# Sh_core.net
KiCad netlist of a schematic drawn in Altium Designer
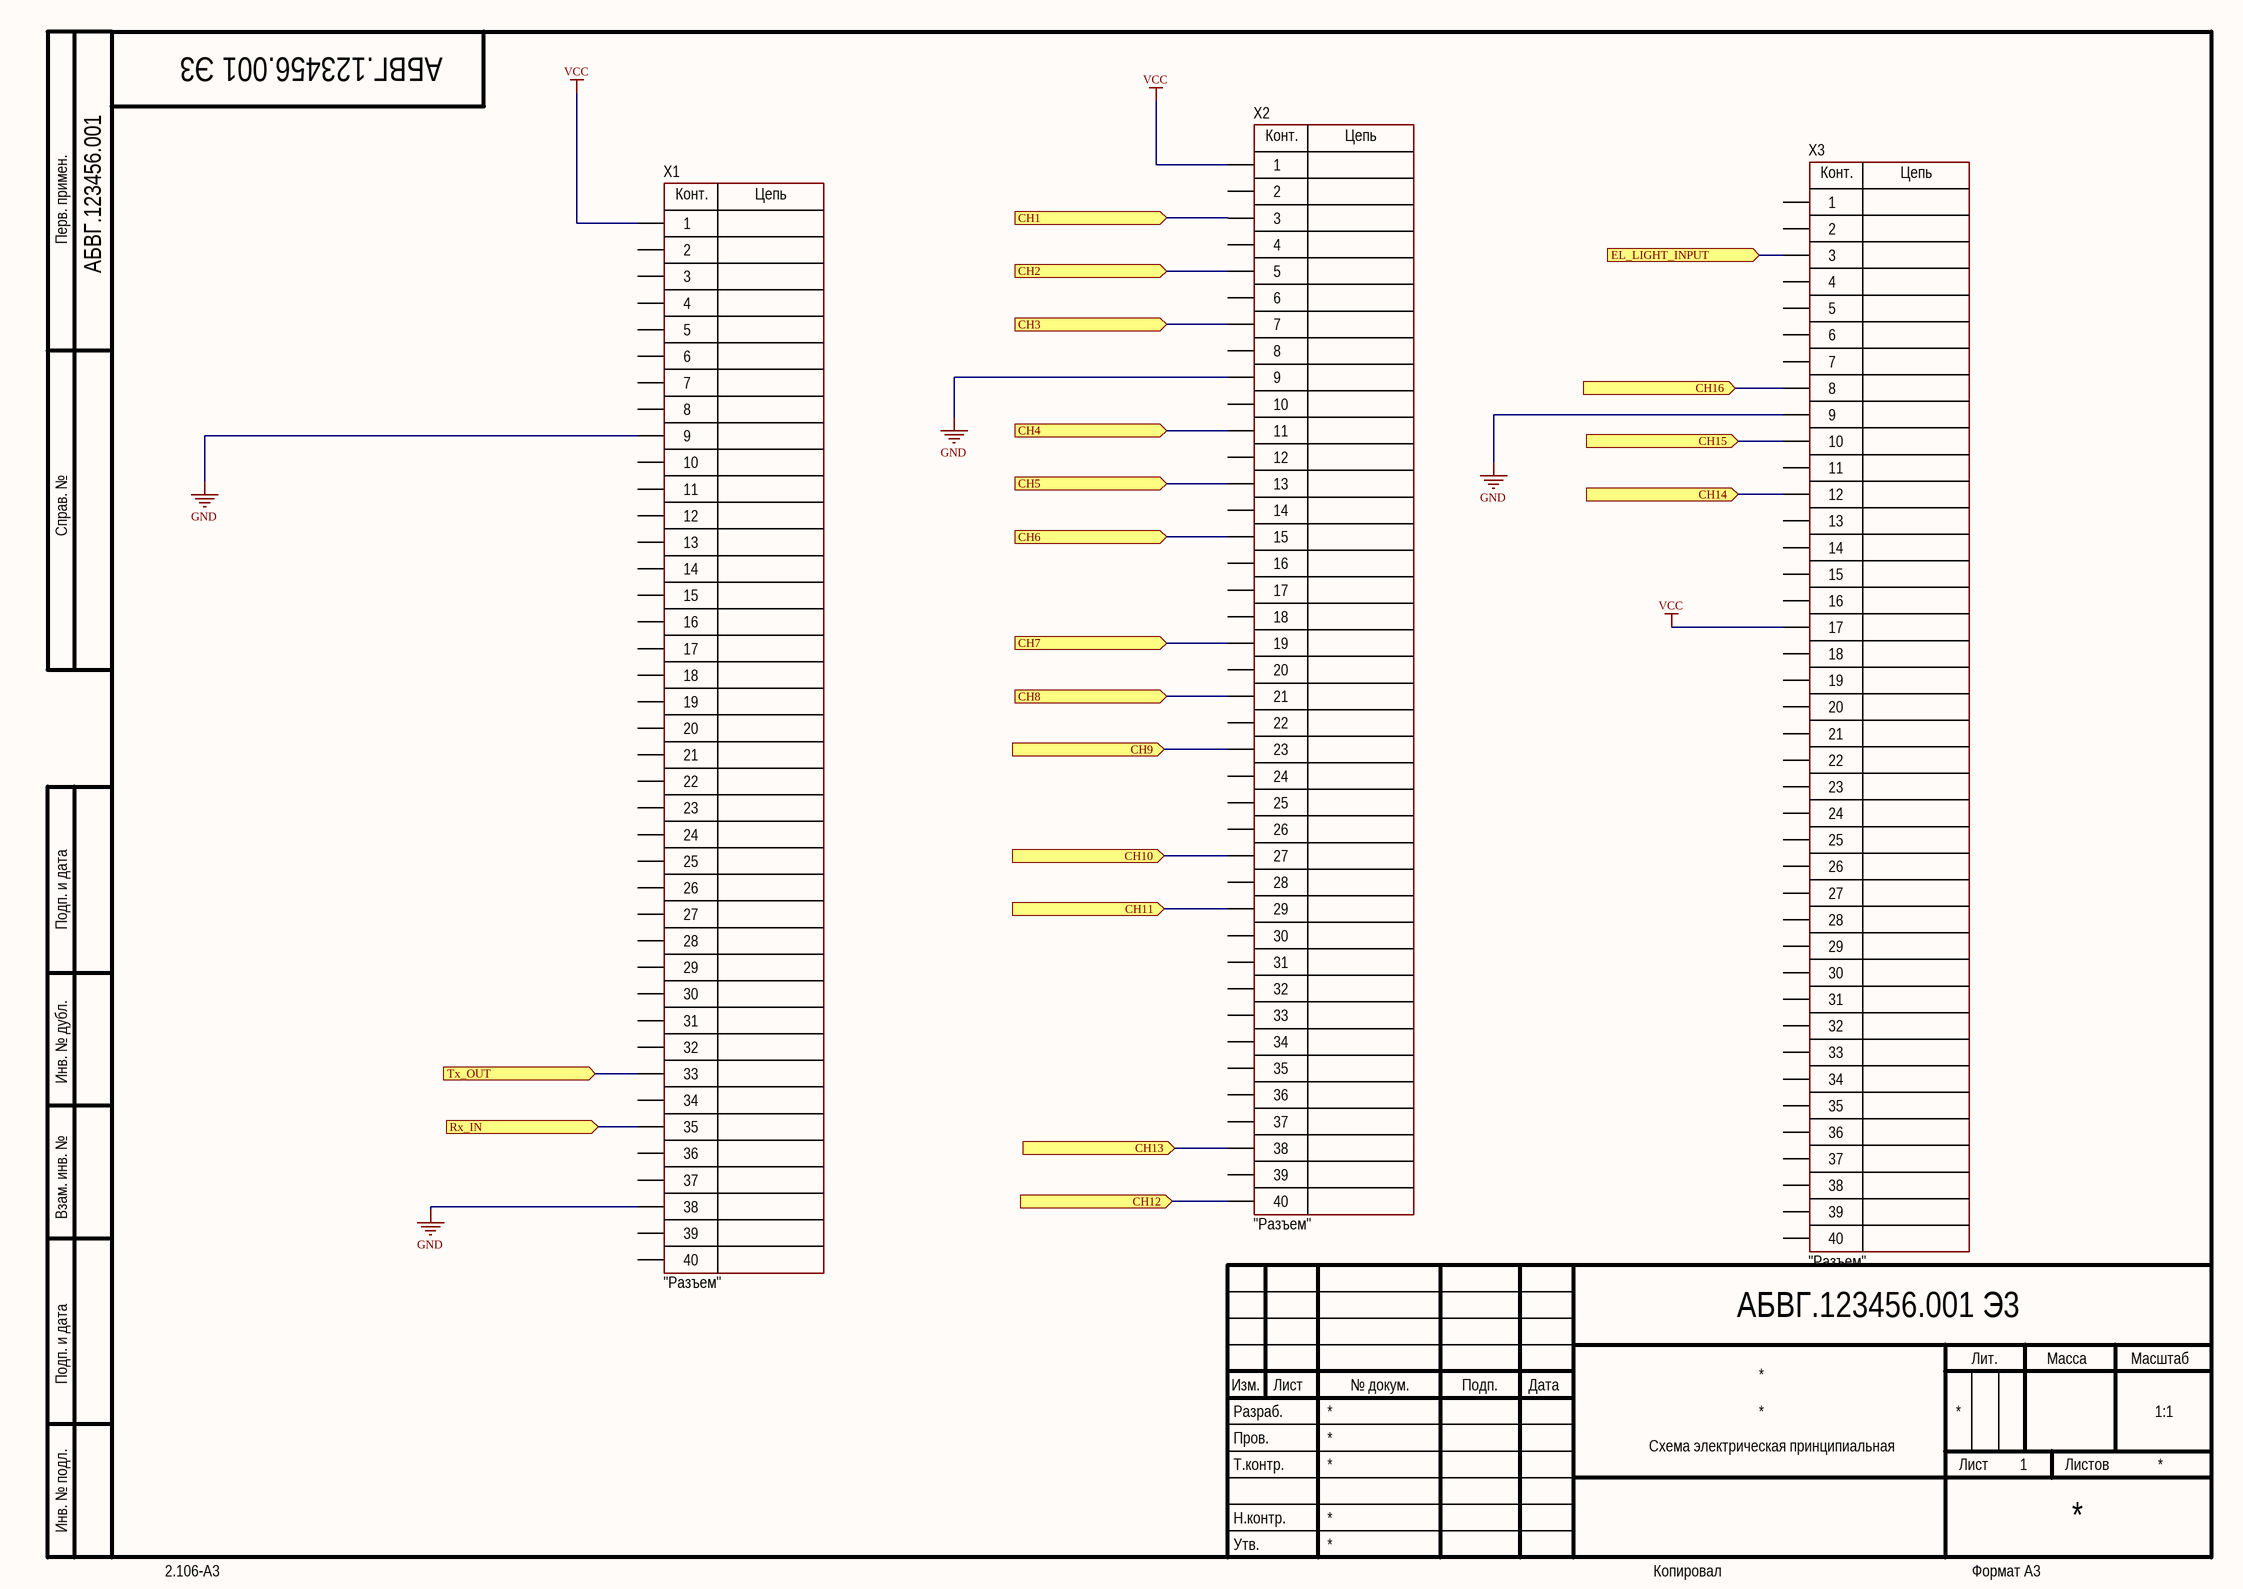
[diagram p0: Sh_core.SchDoc]

(export (version "E")
  (design (tool "Eeschema 10.0.6"))
  (components
    (comp (ref "X1")
      (value "~")
      (footprint "CON: PBD-40 (2.54)")
      (fields
        (field (name "MANUFACTURER") "Connfly")
        (field (name "VALUEMANUFACTURERPARTNUMBER") "Connector, 20pin, 2.54mm, 500VAC, 3A")
        (field (name "PARTNUMBER") "PLS-20")
        (field (name "COMMENTTEXT") "\"Разъем\"")
      )
      (libsource (lib "connector") (part "PBD-40"))
    )
    (comp (ref "X2")
      (value "~")
      (footprint "CON: PBD-40 (2.54)")
      (fields
        (field (name "MANUFACTURER") "Connfly")
        (field (name "VALUEMANUFACTURERPARTNUMBER") "Connector, 20pin, 2.54mm, 500VAC, 3A")
        (field (name "PARTNUMBER") "PLS-20")
        (field (name "COMMENTTEXT") "\"Разъем\"")
      )
      (libsource (lib "connector") (part "PBD-40"))
    )
    (comp (ref "X3")
      (value "~")
      (footprint "CON: PBD-40 (2.54)")
      (fields
        (field (name "MANUFACTURER") "Connfly")
        (field (name "VALUEMANUFACTURERPARTNUMBER") "Connector, 20pin, 2.54mm, 500VAC, 3A")
        (field (name "PARTNUMBER") "PLS-20")
        (field (name "COMMENTTEXT") "\"Разъем\"")
      )
      (libsource (lib "connector") (part "PBD-40"))
    )
  )
  (nets
    (net (code "1") (name "/CH1") (class "Default")
      (node (ref "X2") (pin "3") (pinfunction "3_3") (pintype "passive"))
    )
    (net (code "2") (name "/CH2") (class "Default")
      (node (ref "X2") (pin "5") (pinfunction "5_5") (pintype "passive"))
    )
    (net (code "3") (name "/CH3") (class "Default")
      (node (ref "X2") (pin "7") (pinfunction "7_7") (pintype "passive"))
    )
    (net (code "4") (name "/CH4") (class "Default")
      (node (ref "X2") (pin "11") (pinfunction "11_11") (pintype "passive"))
    )
    (net (code "5") (name "/CH5") (class "Default")
      (node (ref "X2") (pin "13") (pinfunction "13_13") (pintype "passive"))
    )
    (net (code "6") (name "/CH6") (class "Default")
      (node (ref "X2") (pin "15") (pinfunction "15_15") (pintype "passive"))
    )
    (net (code "7") (name "/CH7") (class "Default")
      (node (ref "X2") (pin "19") (pinfunction "19_19") (pintype "passive"))
    )
    (net (code "8") (name "/CH8") (class "Default")
      (node (ref "X2") (pin "21") (pinfunction "21_21") (pintype "passive"))
    )
    (net (code "9") (name "/CH9") (class "Default")
      (node (ref "X2") (pin "23") (pinfunction "23_23") (pintype "passive"))
    )
    (net (code "10") (name "/CH10") (class "Default")
      (node (ref "X2") (pin "27") (pinfunction "27_27") (pintype "passive"))
    )
    (net (code "11") (name "/CH11") (class "Default")
      (node (ref "X2") (pin "29") (pinfunction "29_29") (pintype "passive"))
    )
    (net (code "12") (name "/CH12") (class "Default")
      (node (ref "X2") (pin "40") (pinfunction "40_40") (pintype "passive"))
    )
    (net (code "13") (name "/CH13") (class "Default")
      (node (ref "X2") (pin "38") (pinfunction "38_38") (pintype "passive"))
    )
    (net (code "14") (name "/CH14") (class "Default")
      (node (ref "X3") (pin "12") (pinfunction "12_12") (pintype "passive"))
    )
    (net (code "15") (name "/CH15") (class "Default")
      (node (ref "X3") (pin "10") (pinfunction "10_10") (pintype "passive"))
    )
    (net (code "16") (name "/CH16") (class "Default")
      (node (ref "X3") (pin "8") (pinfunction "8_8") (pintype "passive"))
    )
    (net (code "17") (name "/EL_LIGHT_INPUT") (class "Default")
      (node (ref "X3") (pin "3") (pinfunction "3_3") (pintype "passive"))
    )
    (net (code "18") (name "/Rx_IN") (class "Default")
      (node (ref "X1") (pin "35") (pinfunction "35_35") (pintype "passive"))
    )
    (net (code "19") (name "/Tx_OUT") (class "Default")
      (node (ref "X1") (pin "33") (pinfunction "33_33") (pintype "passive"))
    )
    (net (code "20") (name "GND") (class "Default")
      (node (ref "X1") (pin "38") (pinfunction "38_38") (pintype "passive"))
      (node (ref "X1") (pin "9") (pinfunction "9_9") (pintype "passive"))
      (node (ref "X2") (pin "9") (pinfunction "9_9") (pintype "passive"))
      (node (ref "X3") (pin "9") (pinfunction "9_9") (pintype "passive"))
    )
    (net (code "21") (name "VCC") (class "Default")
      (node (ref "X1") (pin "1") (pinfunction "1_1") (pintype "passive"))
      (node (ref "X2") (pin "1") (pinfunction "1_1") (pintype "passive"))
      (node (ref "X3") (pin "17") (pinfunction "17_17") (pintype "passive"))
    )
    (net (code "22") (name "unconnected-(X1-Pad2)") (class "Default")
      (node (ref "X1") (pin "2") (pinfunction "2_2") (pintype "passive"))
    )
    (net (code "23") (name "unconnected-(X1-Pad3)") (class "Default")
      (node (ref "X1") (pin "3") (pinfunction "3_3") (pintype "passive"))
    )
    (net (code "24") (name "unconnected-(X1-Pad4)") (class "Default")
      (node (ref "X1") (pin "4") (pinfunction "4_4") (pintype "passive"))
    )
    (net (code "25") (name "unconnected-(X1-Pad5)") (class "Default")
      (node (ref "X1") (pin "5") (pinfunction "5_5") (pintype "passive"))
    )
    (net (code "26") (name "unconnected-(X1-Pad6)") (class "Default")
      (node (ref "X1") (pin "6") (pinfunction "6_6") (pintype "passive"))
    )
    (net (code "27") (name "unconnected-(X1-Pad7)") (class "Default")
      (node (ref "X1") (pin "7") (pinfunction "7_7") (pintype "passive"))
    )
    (net (code "28") (name "unconnected-(X1-Pad8)") (class "Default")
      (node (ref "X1") (pin "8") (pinfunction "8_8") (pintype "passive"))
    )
    (net (code "29") (name "unconnected-(X1-Pad10)") (class "Default")
      (node (ref "X1") (pin "10") (pinfunction "10_10") (pintype "passive"))
    )
    (net (code "30") (name "unconnected-(X1-Pad11)") (class "Default")
      (node (ref "X1") (pin "11") (pinfunction "11_11") (pintype "passive"))
    )
    (net (code "31") (name "unconnected-(X1-Pad12)") (class "Default")
      (node (ref "X1") (pin "12") (pinfunction "12_12") (pintype "passive"))
    )
    (net (code "32") (name "unconnected-(X1-Pad13)") (class "Default")
      (node (ref "X1") (pin "13") (pinfunction "13_13") (pintype "passive"))
    )
    (net (code "33") (name "unconnected-(X1-Pad14)") (class "Default")
      (node (ref "X1") (pin "14") (pinfunction "14_14") (pintype "passive"))
    )
    (net (code "34") (name "unconnected-(X1-Pad15)") (class "Default")
      (node (ref "X1") (pin "15") (pinfunction "15_15") (pintype "passive"))
    )
    (net (code "35") (name "unconnected-(X1-Pad16)") (class "Default")
      (node (ref "X1") (pin "16") (pinfunction "16_16") (pintype "passive"))
    )
    (net (code "36") (name "unconnected-(X1-Pad17)") (class "Default")
      (node (ref "X1") (pin "17") (pinfunction "17_17") (pintype "passive"))
    )
    (net (code "37") (name "unconnected-(X1-Pad18)") (class "Default")
      (node (ref "X1") (pin "18") (pinfunction "18_18") (pintype "passive"))
    )
    (net (code "38") (name "unconnected-(X1-Pad19)") (class "Default")
      (node (ref "X1") (pin "19") (pinfunction "19_19") (pintype "passive"))
    )
    (net (code "39") (name "unconnected-(X1-Pad20)") (class "Default")
      (node (ref "X1") (pin "20") (pinfunction "20_20") (pintype "passive"))
    )
    (net (code "40") (name "unconnected-(X1-Pad21)") (class "Default")
      (node (ref "X1") (pin "21") (pinfunction "21_21") (pintype "passive"))
    )
    (net (code "41") (name "unconnected-(X1-Pad22)") (class "Default")
      (node (ref "X1") (pin "22") (pinfunction "22_22") (pintype "passive"))
    )
    (net (code "42") (name "unconnected-(X1-Pad23)") (class "Default")
      (node (ref "X1") (pin "23") (pinfunction "23_23") (pintype "passive"))
    )
    (net (code "43") (name "unconnected-(X1-Pad24)") (class "Default")
      (node (ref "X1") (pin "24") (pinfunction "24_24") (pintype "passive"))
    )
    (net (code "44") (name "unconnected-(X1-Pad25)") (class "Default")
      (node (ref "X1") (pin "25") (pinfunction "25_25") (pintype "passive"))
    )
    (net (code "45") (name "unconnected-(X1-Pad26)") (class "Default")
      (node (ref "X1") (pin "26") (pinfunction "26_26") (pintype "passive"))
    )
    (net (code "46") (name "unconnected-(X1-Pad27)") (class "Default")
      (node (ref "X1") (pin "27") (pinfunction "27_27") (pintype "passive"))
    )
    (net (code "47") (name "unconnected-(X1-Pad28)") (class "Default")
      (node (ref "X1") (pin "28") (pinfunction "28_28") (pintype "passive"))
    )
    (net (code "48") (name "unconnected-(X1-Pad29)") (class "Default")
      (node (ref "X1") (pin "29") (pinfunction "29_29") (pintype "passive"))
    )
    (net (code "49") (name "unconnected-(X1-Pad30)") (class "Default")
      (node (ref "X1") (pin "30") (pinfunction "30_30") (pintype "passive"))
    )
    (net (code "50") (name "unconnected-(X1-Pad31)") (class "Default")
      (node (ref "X1") (pin "31") (pinfunction "31_31") (pintype "passive"))
    )
    (net (code "51") (name "unconnected-(X1-Pad32)") (class "Default")
      (node (ref "X1") (pin "32") (pinfunction "32_32") (pintype "passive"))
    )
    (net (code "52") (name "unconnected-(X1-Pad34)") (class "Default")
      (node (ref "X1") (pin "34") (pinfunction "34_34") (pintype "passive"))
    )
    (net (code "53") (name "unconnected-(X1-Pad36)") (class "Default")
      (node (ref "X1") (pin "36") (pinfunction "36_36") (pintype "passive"))
    )
    (net (code "54") (name "unconnected-(X1-Pad37)") (class "Default")
      (node (ref "X1") (pin "37") (pinfunction "37_37") (pintype "passive"))
    )
    (net (code "55") (name "unconnected-(X1-Pad39)") (class "Default")
      (node (ref "X1") (pin "39") (pinfunction "39_39") (pintype "passive"))
    )
    (net (code "56") (name "unconnected-(X1-Pad40)") (class "Default")
      (node (ref "X1") (pin "40") (pinfunction "40_40") (pintype "passive"))
    )
    (net (code "57") (name "unconnected-(X2-Pad2)") (class "Default")
      (node (ref "X2") (pin "2") (pinfunction "2_2") (pintype "passive"))
    )
    (net (code "58") (name "unconnected-(X2-Pad4)") (class "Default")
      (node (ref "X2") (pin "4") (pinfunction "4_4") (pintype "passive"))
    )
    (net (code "59") (name "unconnected-(X2-Pad6)") (class "Default")
      (node (ref "X2") (pin "6") (pinfunction "6_6") (pintype "passive"))
    )
    (net (code "60") (name "unconnected-(X2-Pad8)") (class "Default")
      (node (ref "X2") (pin "8") (pinfunction "8_8") (pintype "passive"))
    )
    (net (code "61") (name "unconnected-(X2-Pad10)") (class "Default")
      (node (ref "X2") (pin "10") (pinfunction "10_10") (pintype "passive"))
    )
    (net (code "62") (name "unconnected-(X2-Pad12)") (class "Default")
      (node (ref "X2") (pin "12") (pinfunction "12_12") (pintype "passive"))
    )
    (net (code "63") (name "unconnected-(X2-Pad14)") (class "Default")
      (node (ref "X2") (pin "14") (pinfunction "14_14") (pintype "passive"))
    )
    (net (code "64") (name "unconnected-(X2-Pad16)") (class "Default")
      (node (ref "X2") (pin "16") (pinfunction "16_16") (pintype "passive"))
    )
    (net (code "65") (name "unconnected-(X2-Pad17)") (class "Default")
      (node (ref "X2") (pin "17") (pinfunction "17_17") (pintype "passive"))
    )
    (net (code "66") (name "unconnected-(X2-Pad18)") (class "Default")
      (node (ref "X2") (pin "18") (pinfunction "18_18") (pintype "passive"))
    )
    (net (code "67") (name "unconnected-(X2-Pad20)") (class "Default")
      (node (ref "X2") (pin "20") (pinfunction "20_20") (pintype "passive"))
    )
    (net (code "68") (name "unconnected-(X2-Pad22)") (class "Default")
      (node (ref "X2") (pin "22") (pinfunction "22_22") (pintype "passive"))
    )
    (net (code "69") (name "unconnected-(X2-Pad24)") (class "Default")
      (node (ref "X2") (pin "24") (pinfunction "24_24") (pintype "passive"))
    )
    (net (code "70") (name "unconnected-(X2-Pad25)") (class "Default")
      (node (ref "X2") (pin "25") (pinfunction "25_25") (pintype "passive"))
    )
    (net (code "71") (name "unconnected-(X2-Pad26)") (class "Default")
      (node (ref "X2") (pin "26") (pinfunction "26_26") (pintype "passive"))
    )
    (net (code "72") (name "unconnected-(X2-Pad28)") (class "Default")
      (node (ref "X2") (pin "28") (pinfunction "28_28") (pintype "passive"))
    )
    (net (code "73") (name "unconnected-(X2-Pad30)") (class "Default")
      (node (ref "X2") (pin "30") (pinfunction "30_30") (pintype "passive"))
    )
    (net (code "74") (name "unconnected-(X2-Pad31)") (class "Default")
      (node (ref "X2") (pin "31") (pinfunction "31_31") (pintype "passive"))
    )
    (net (code "75") (name "unconnected-(X2-Pad32)") (class "Default")
      (node (ref "X2") (pin "32") (pinfunction "32_32") (pintype "passive"))
    )
    (net (code "76") (name "unconnected-(X2-Pad33)") (class "Default")
      (node (ref "X2") (pin "33") (pinfunction "33_33") (pintype "passive"))
    )
    (net (code "77") (name "unconnected-(X2-Pad34)") (class "Default")
      (node (ref "X2") (pin "34") (pinfunction "34_34") (pintype "passive"))
    )
    (net (code "78") (name "unconnected-(X2-Pad35)") (class "Default")
      (node (ref "X2") (pin "35") (pinfunction "35_35") (pintype "passive"))
    )
    (net (code "79") (name "unconnected-(X2-Pad36)") (class "Default")
      (node (ref "X2") (pin "36") (pinfunction "36_36") (pintype "passive"))
    )
    (net (code "80") (name "unconnected-(X2-Pad37)") (class "Default")
      (node (ref "X2") (pin "37") (pinfunction "37_37") (pintype "passive"))
    )
    (net (code "81") (name "unconnected-(X2-Pad39)") (class "Default")
      (node (ref "X2") (pin "39") (pinfunction "39_39") (pintype "passive"))
    )
    (net (code "82") (name "unconnected-(X3-Pad1)") (class "Default")
      (node (ref "X3") (pin "1") (pinfunction "1_1") (pintype "passive"))
    )
    (net (code "83") (name "unconnected-(X3-Pad2)") (class "Default")
      (node (ref "X3") (pin "2") (pinfunction "2_2") (pintype "passive"))
    )
    (net (code "84") (name "unconnected-(X3-Pad4)") (class "Default")
      (node (ref "X3") (pin "4") (pinfunction "4_4") (pintype "passive"))
    )
    (net (code "85") (name "unconnected-(X3-Pad5)") (class "Default")
      (node (ref "X3") (pin "5") (pinfunction "5_5") (pintype "passive"))
    )
    (net (code "86") (name "unconnected-(X3-Pad6)") (class "Default")
      (node (ref "X3") (pin "6") (pinfunction "6_6") (pintype "passive"))
    )
    (net (code "87") (name "unconnected-(X3-Pad7)") (class "Default")
      (node (ref "X3") (pin "7") (pinfunction "7_7") (pintype "passive"))
    )
    (net (code "88") (name "unconnected-(X3-Pad11)") (class "Default")
      (node (ref "X3") (pin "11") (pinfunction "11_11") (pintype "passive"))
    )
    (net (code "89") (name "unconnected-(X3-Pad13)") (class "Default")
      (node (ref "X3") (pin "13") (pinfunction "13_13") (pintype "passive"))
    )
    (net (code "90") (name "unconnected-(X3-Pad14)") (class "Default")
      (node (ref "X3") (pin "14") (pinfunction "14_14") (pintype "passive"))
    )
    (net (code "91") (name "unconnected-(X3-Pad15)") (class "Default")
      (node (ref "X3") (pin "15") (pinfunction "15_15") (pintype "passive"))
    )
    (net (code "92") (name "unconnected-(X3-Pad16)") (class "Default")
      (node (ref "X3") (pin "16") (pinfunction "16_16") (pintype "passive"))
    )
    (net (code "93") (name "unconnected-(X3-Pad18)") (class "Default")
      (node (ref "X3") (pin "18") (pinfunction "18_18") (pintype "passive"))
    )
    (net (code "94") (name "unconnected-(X3-Pad19)") (class "Default")
      (node (ref "X3") (pin "19") (pinfunction "19_19") (pintype "passive"))
    )
    (net (code "95") (name "unconnected-(X3-Pad20)") (class "Default")
      (node (ref "X3") (pin "20") (pinfunction "20_20") (pintype "passive"))
    )
    (net (code "96") (name "unconnected-(X3-Pad21)") (class "Default")
      (node (ref "X3") (pin "21") (pinfunction "21_21") (pintype "passive"))
    )
    (net (code "97") (name "unconnected-(X3-Pad22)") (class "Default")
      (node (ref "X3") (pin "22") (pinfunction "22_22") (pintype "passive"))
    )
    (net (code "98") (name "unconnected-(X3-Pad23)") (class "Default")
      (node (ref "X3") (pin "23") (pinfunction "23_23") (pintype "passive"))
    )
    (net (code "99") (name "unconnected-(X3-Pad24)") (class "Default")
      (node (ref "X3") (pin "24") (pinfunction "24_24") (pintype "passive"))
    )
    (net (code "100") (name "unconnected-(X3-Pad25)") (class "Default")
      (node (ref "X3") (pin "25") (pinfunction "25_25") (pintype "passive"))
    )
    (net (code "101") (name "unconnected-(X3-Pad26)") (class "Default")
      (node (ref "X3") (pin "26") (pinfunction "26_26") (pintype "passive"))
    )
    (net (code "102") (name "unconnected-(X3-Pad27)") (class "Default")
      (node (ref "X3") (pin "27") (pinfunction "27_27") (pintype "passive"))
    )
    (net (code "103") (name "unconnected-(X3-Pad28)") (class "Default")
      (node (ref "X3") (pin "28") (pinfunction "28_28") (pintype "passive"))
    )
    (net (code "104") (name "unconnected-(X3-Pad29)") (class "Default")
      (node (ref "X3") (pin "29") (pinfunction "29_29") (pintype "passive"))
    )
    (net (code "105") (name "unconnected-(X3-Pad30)") (class "Default")
      (node (ref "X3") (pin "30") (pinfunction "30_30") (pintype "passive"))
    )
    (net (code "106") (name "unconnected-(X3-Pad31)") (class "Default")
      (node (ref "X3") (pin "31") (pinfunction "31_31") (pintype "passive"))
    )
    (net (code "107") (name "unconnected-(X3-Pad32)") (class "Default")
      (node (ref "X3") (pin "32") (pinfunction "32_32") (pintype "passive"))
    )
    (net (code "108") (name "unconnected-(X3-Pad33)") (class "Default")
      (node (ref "X3") (pin "33") (pinfunction "33_33") (pintype "passive"))
    )
    (net (code "109") (name "unconnected-(X3-Pad34)") (class "Default")
      (node (ref "X3") (pin "34") (pinfunction "34_34") (pintype "passive"))
    )
    (net (code "110") (name "unconnected-(X3-Pad35)") (class "Default")
      (node (ref "X3") (pin "35") (pinfunction "35_35") (pintype "passive"))
    )
    (net (code "111") (name "unconnected-(X3-Pad36)") (class "Default")
      (node (ref "X3") (pin "36") (pinfunction "36_36") (pintype "passive"))
    )
    (net (code "112") (name "unconnected-(X3-Pad37)") (class "Default")
      (node (ref "X3") (pin "37") (pinfunction "37_37") (pintype "passive"))
    )
    (net (code "113") (name "unconnected-(X3-Pad38)") (class "Default")
      (node (ref "X3") (pin "38") (pinfunction "38_38") (pintype "passive"))
    )
    (net (code "114") (name "unconnected-(X3-Pad39)") (class "Default")
      (node (ref "X3") (pin "39") (pinfunction "39_39") (pintype "passive"))
    )
    (net (code "115") (name "unconnected-(X3-Pad40)") (class "Default")
      (node (ref "X3") (pin "40") (pinfunction "40_40") (pintype "passive"))
    )
  )
)
